# msp430_cool.net
KiCad netlist of a schematic drawn in EAGLE
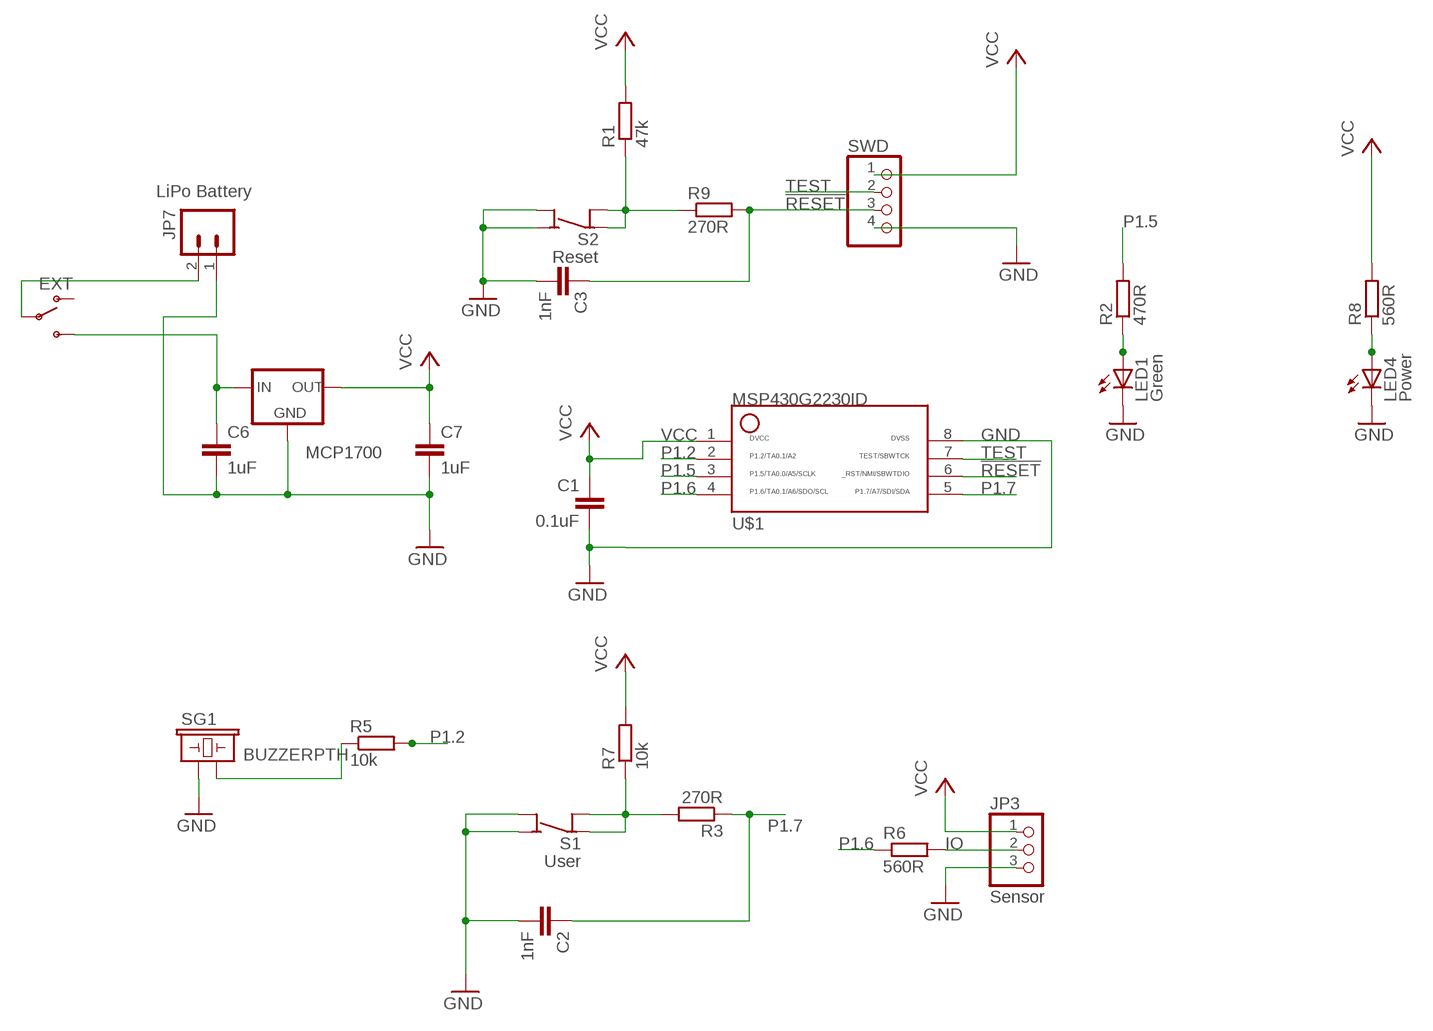
[diagram p0: schematic, sheet 1]

(export (version "E")
  (design (tool "Eeschema 10.0.6"))
  (components
    (comp (ref "C1")
      (value "0.1uF")
      (footprint "eagle-import:C0805")
      (libsource (lib "eagle-import") (part "C-EUC0805"))
    )
    (comp (ref "C2")
      (value "1nF")
      (footprint "eagle-import:C0805")
      (libsource (lib "eagle-import") (part "C-EUC0805"))
    )
    (comp (ref "C3")
      (value "1nF")
      (footprint "eagle-import:C0805")
      (libsource (lib "eagle-import") (part "C-EUC0805"))
    )
    (comp (ref "C6")
      (value "1uF")
      (footprint "eagle-import:C0805")
      (libsource (lib "eagle-import") (part "C-EUC0805"))
    )
    (comp (ref "C7")
      (value "1uF")
      (footprint "eagle-import:C0805")
      (libsource (lib "eagle-import") (part "C-EUC0805"))
    )
    (comp (ref "JP3")
      (value "Sensor")
      (footprint "eagle-import:1X03")
      (libsource (lib "eagle-import") (part "PINHD-1X3"))
    )
    (comp (ref "JP7")
      (value "LiPo Battery")
      (footprint "eagle-import:JST-2-PTH")
      (libsource (lib "eagle-import") (part "M02JST-PTH-2"))
    )
    (comp (ref "LED1")
      (value "Green")
      (footprint "eagle-import:CHIPLED_1206")
      (libsource (lib "eagle-import") (part "LEDCHIPLED_1206"))
    )
    (comp (ref "LED4")
      (value "Power")
      (footprint "eagle-import:CHIPLED_1206")
      (libsource (lib "eagle-import") (part "LEDCHIPLED_1206"))
    )
    (comp (ref "MCP1700")
      (value "MCP1700")
      (footprint "eagle-import:SOT-23")
      (libsource (lib "eagle-import") (part "MCP1700SOT-23"))
    )
    (comp (ref "ON")
      (value "EXT")
      (footprint "eagle-import:SWITCH-SPDT")
      (libsource (lib "eagle-import") (part "SWITCH-SPSTPTH"))
    )
    (comp (ref "R1")
      (value "47k")
      (footprint "eagle-import:R0805")
      (libsource (lib "eagle-import") (part "R-EU_R0805"))
    )
    (comp (ref "R2")
      (value "470R")
      (footprint "eagle-import:R0805")
      (libsource (lib "eagle-import") (part "R-EU_R0805"))
    )
    (comp (ref "R3")
      (value "270R")
      (footprint "eagle-import:R0805")
      (libsource (lib "eagle-import") (part "R-EU_R0805"))
    )
    (comp (ref "R5")
      (value "10k")
      (footprint "eagle-import:R0805")
      (libsource (lib "eagle-import") (part "R-EU_R0805"))
    )
    (comp (ref "R6")
      (value "560R")
      (footprint "eagle-import:R0805")
      (libsource (lib "eagle-import") (part "R-EU_R0805"))
    )
    (comp (ref "R7")
      (value "10k")
      (footprint "eagle-import:R0805")
      (libsource (lib "eagle-import") (part "R-EU_R0805"))
    )
    (comp (ref "R8")
      (value "560R")
      (footprint "eagle-import:R0805")
      (libsource (lib "eagle-import") (part "R-EU_R0805"))
    )
    (comp (ref "R9")
      (value "270R")
      (footprint "eagle-import:R0805")
      (libsource (lib "eagle-import") (part "R-EU_R0805"))
    )
    (comp (ref "S1")
      (value "User")
      (footprint "eagle-import:6MMTACTILE_4PIN")
      (libsource (lib "eagle-import") (part "SPST4"))
    )
    (comp (ref "S2")
      (value "Reset")
      (footprint "eagle-import:6MMTACTILE_4PIN")
      (libsource (lib "eagle-import") (part "SPST4"))
    )
    (comp (ref "SG1")
      (value "BUZZERPTH")
      (footprint "eagle-import:BUZZER-12MM")
      (libsource (lib "eagle-import") (part "BUZZERPTH"))
    )
    (comp (ref "SWD")
      (value "PINHD-1X4")
      (footprint "eagle-import:1X04")
      (libsource (lib "eagle-import") (part "PINHD-1X4"))
    )
    (comp (ref "U$1")
      (value "MSP430G2230ID")
      (footprint "eagle-import:SO08")
      (libsource (lib "eagle-import") (part "MSP430G2230ID"))
    )
  )
  (nets
    (net (code "1") (name "/IO") (class "Default")
      (node (ref "JP3") (pin "2") (pinfunction "2_2") (pintype "passive"))
      (node (ref "R6") (pin "2") (pinfunction "2_2") (pintype "passive"))
    )
    (net (code "2") (name "/P1.2") (class "Default")
      (node (ref "R5") (pin "2") (pinfunction "2_2") (pintype "passive"))
      (node (ref "U$1") (pin "2") (pinfunction "2_2") (pintype "bidirectional"))
    )
    (net (code "3") (name "/P1.5") (class "Default")
      (node (ref "R2") (pin "2") (pinfunction "2_2") (pintype "passive"))
      (node (ref "U$1") (pin "3") (pinfunction "3_3") (pintype "bidirectional"))
    )
    (net (code "4") (name "/P1.6") (class "Default")
      (node (ref "R6") (pin "1") (pinfunction "1_1") (pintype "passive"))
      (node (ref "U$1") (pin "4") (pinfunction "4_4") (pintype "bidirectional"))
    )
    (net (code "5") (name "/P1.7") (class "Default")
      (node (ref "C2") (pin "1") (pinfunction "1_1") (pintype "passive"))
      (node (ref "R3") (pin "1") (pinfunction "1_1") (pintype "passive"))
      (node (ref "U$1") (pin "5") (pinfunction "5_5") (pintype "bidirectional"))
    )
    (net (code "6") (name "/TEST") (class "Default")
      (node (ref "SWD") (pin "2") (pinfunction "2_2") (pintype "passive"))
      (node (ref "U$1") (pin "7") (pinfunction "7_7") (pintype "bidirectional"))
    )
    (net (code "7") (name "/~{RESET}") (class "Default")
      (node (ref "C3") (pin "1") (pinfunction "1_1") (pintype "passive"))
      (node (ref "R9") (pin "2") (pinfunction "2_2") (pintype "passive"))
      (node (ref "SWD") (pin "3") (pinfunction "3_3") (pintype "passive"))
      (node (ref "U$1") (pin "6") (pinfunction "6_6") (pintype "bidirectional"))
    )
    (net (code "8") (name "GND") (class "Default")
      (node (ref "C1") (pin "2") (pinfunction "2_2") (pintype "passive"))
      (node (ref "C2") (pin "2") (pinfunction "2_2") (pintype "passive"))
      (node (ref "C3") (pin "2") (pinfunction "2_2") (pintype "passive"))
      (node (ref "C6") (pin "2") (pinfunction "2_2") (pintype "passive"))
      (node (ref "C7") (pin "2") (pinfunction "2_2") (pintype "passive"))
      (node (ref "JP3") (pin "3") (pinfunction "3_3") (pintype "passive"))
      (node (ref "JP7") (pin "1") (pinfunction "1_1") (pintype "passive"))
      (node (ref "LED1") (pin "C") (pinfunction "C_C") (pintype "passive"))
      (node (ref "LED4") (pin "C") (pinfunction "C_C") (pintype "passive"))
      (node (ref "MCP1700") (pin "1") (pinfunction "GND_1") (pintype "input"))
      (node (ref "S1") (pin "A1") (pinfunction "NO_A1") (pintype "passive"))
      (node (ref "S1") (pin "A2") (pinfunction "NO_A2") (pintype "passive"))
      (node (ref "S2") (pin "A1") (pinfunction "NO_A1") (pintype "passive"))
      (node (ref "S2") (pin "A2") (pinfunction "NO_A2") (pintype "passive"))
      (node (ref "SG1") (pin "+") (pinfunction "1_+") (pintype "passive"))
      (node (ref "SWD") (pin "4") (pinfunction "4_4") (pintype "passive"))
      (node (ref "U$1") (pin "8") (pinfunction "8_8") (pintype "power_in"))
    )
    (net (code "9") (name "Net-(LED1-PadA)") (class "Default")
      (node (ref "LED1") (pin "A") (pinfunction "A_A") (pintype "passive"))
      (node (ref "R2") (pin "1") (pinfunction "1_1") (pintype "passive"))
    )
    (net (code "10") (name "Net-(LED4-PadA)") (class "Default")
      (node (ref "LED4") (pin "A") (pinfunction "A_A") (pintype "passive"))
      (node (ref "R8") (pin "1") (pinfunction "1_1") (pintype "passive"))
    )
    (net (code "11") (name "Net-(MCP1700-IN)") (class "Default")
      (node (ref "C6") (pin "1") (pinfunction "1_1") (pintype "passive"))
      (node (ref "MCP1700") (pin "3") (pinfunction "IN_3") (pintype "input"))
      (node (ref "ON") (pin "3") (pinfunction "S_3") (pintype "passive"))
    )
    (net (code "12") (name "Net-(ON-P)") (class "Default")
      (node (ref "JP7") (pin "2") (pinfunction "2_2") (pintype "passive"))
      (node (ref "ON") (pin "2") (pinfunction "P_2") (pintype "passive"))
    )
    (net (code "13") (name "Net-(R1-Pad1)") (class "Default")
      (node (ref "R1") (pin "1") (pinfunction "1_1") (pintype "passive"))
      (node (ref "R9") (pin "1") (pinfunction "1_1") (pintype "passive"))
      (node (ref "S2") (pin "B1") (pinfunction "COM_B1") (pintype "passive"))
      (node (ref "S2") (pin "B2") (pinfunction "COM_B2") (pintype "passive"))
    )
    (net (code "14") (name "Net-(R3-Pad2)") (class "Default")
      (node (ref "R3") (pin "2") (pinfunction "2_2") (pintype "passive"))
      (node (ref "R7") (pin "1") (pinfunction "1_1") (pintype "passive"))
      (node (ref "S1") (pin "B1") (pinfunction "COM_B1") (pintype "passive"))
      (node (ref "S1") (pin "B2") (pinfunction "COM_B2") (pintype "passive"))
    )
    (net (code "15") (name "Net-(SG1-2)") (class "Default")
      (node (ref "R5") (pin "1") (pinfunction "1_1") (pintype "passive"))
      (node (ref "SG1") (pin "-") (pinfunction "2_-") (pintype "passive"))
    )
    (net (code "16") (name "VCC") (class "Default")
      (node (ref "C1") (pin "1") (pinfunction "1_1") (pintype "passive"))
      (node (ref "C7") (pin "1") (pinfunction "1_1") (pintype "passive"))
      (node (ref "JP3") (pin "1") (pinfunction "1_1") (pintype "passive"))
      (node (ref "MCP1700") (pin "2") (pinfunction "OUT_2") (pintype "passive"))
      (node (ref "R1") (pin "2") (pinfunction "2_2") (pintype "passive"))
      (node (ref "R7") (pin "2") (pinfunction "2_2") (pintype "passive"))
      (node (ref "R8") (pin "2") (pinfunction "2_2") (pintype "passive"))
      (node (ref "SWD") (pin "1") (pinfunction "1_1") (pintype "passive"))
      (node (ref "U$1") (pin "1") (pinfunction "1_1") (pintype "power_in"))
    )
    (net (code "17") (name "unconnected-(ON-O-Pad1)") (class "Default")
      (node (ref "ON") (pin "1") (pinfunction "O_1") (pintype "passive"))
    )
  )
)
